# Tachometer-with-4x7-Segm-LED-Display.net
KiCad netlist of a schematic drawn in EAGLE
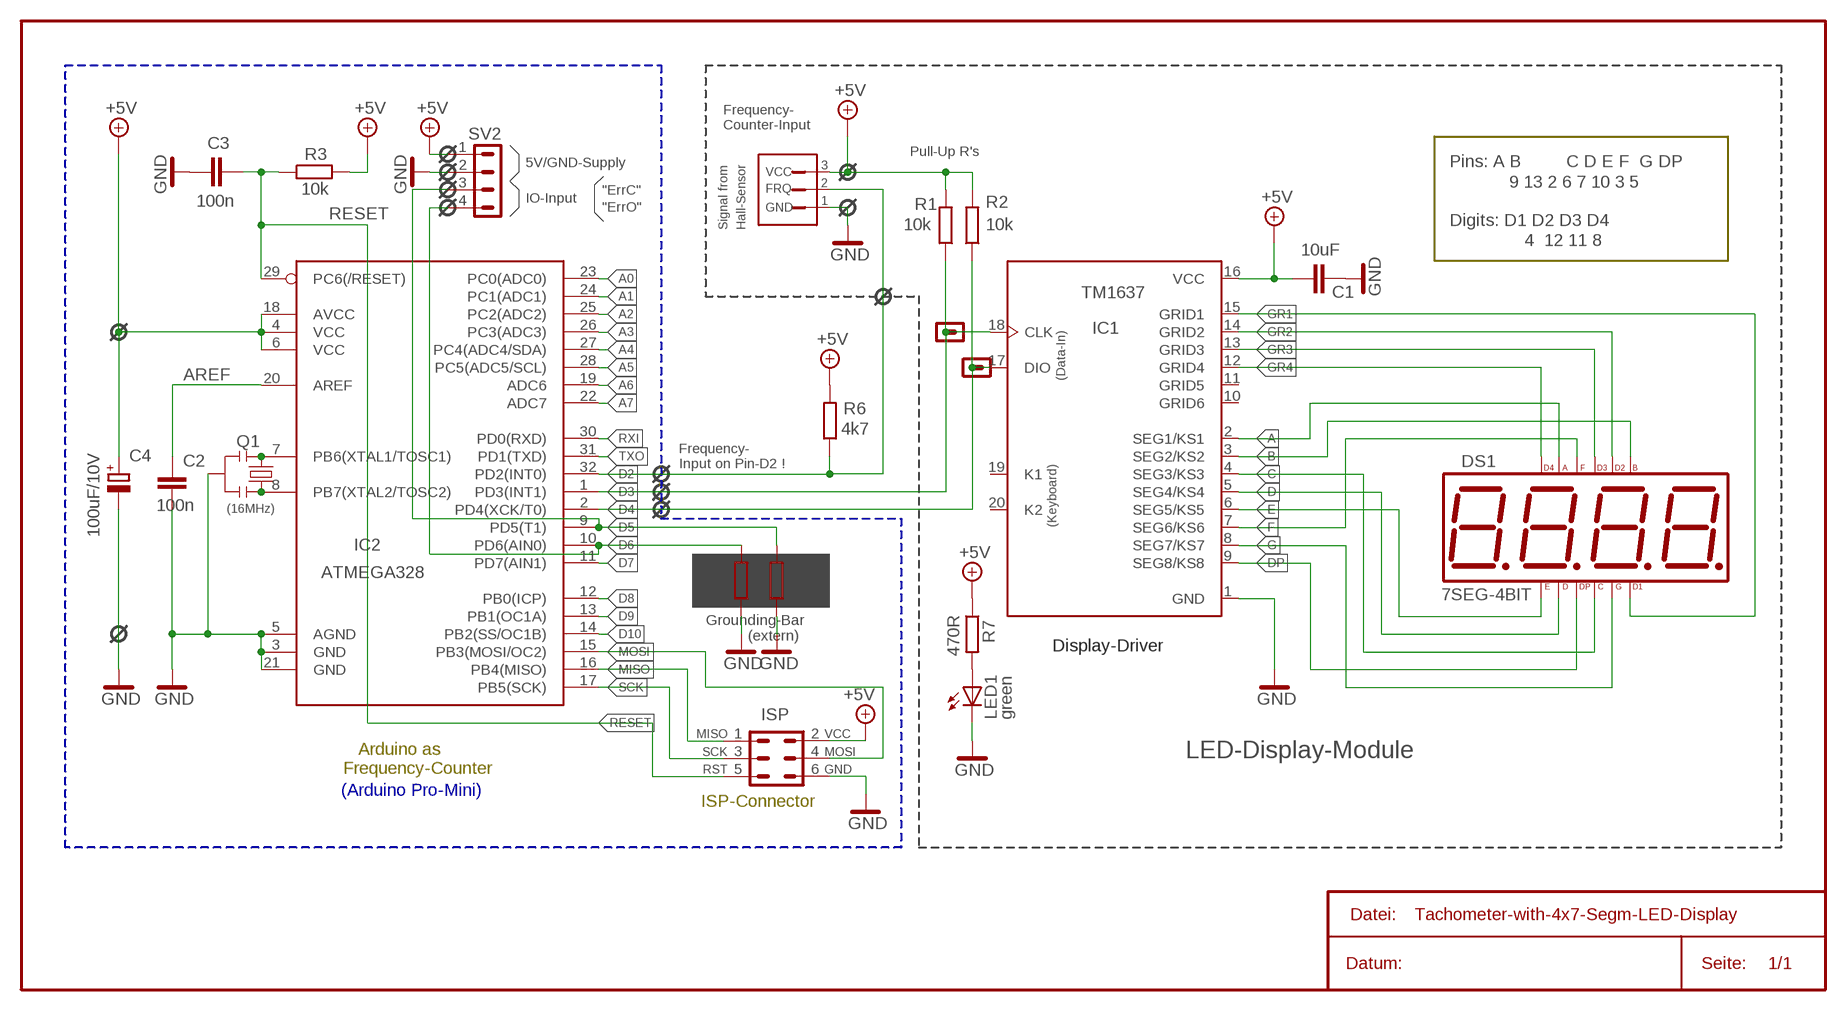
[diagram p0: schematic, sheet 1]

(export (version "E")
  (design (tool "Eeschema 10.0.6"))
  (components
    (comp (ref "C1")
      (value "10uF")
      (footprint "eagle-import:C0805")
      (libsource (lib "eagle-import") (part "C-EUC0805"))
    )
    (comp (ref "C2")
      (value "100n")
      (footprint "eagle-import:C0603")
      (libsource (lib "eagle-import") (part "C-EUC0603"))
    )
    (comp (ref "C3")
      (value "100n")
      (footprint "eagle-import:C0603")
      (libsource (lib "eagle-import") (part "C-EUC0603"))
    )
    (comp (ref "C4")
      (value "100uF/10V")
      (footprint "eagle-import:E2,5-7")
      (libsource (lib "eagle-import") (part "CPOL-EUE2.5-7"))
    )
    (comp (ref "DS1")
      (value "7SEG-4BIT")
      (footprint "eagle-import:7SEG-14-4BIT")
      (libsource (lib "eagle-import") (part "7SEG-4BT"))
    )
    (comp (ref "H")
      (value "Hall-Ss.")
      (footprint "eagle-import:3JST-XH")
      (libsource (lib "eagle-import") (part "3JST-XH"))
    )
    (comp (ref "IC1")
      (value "TM1637")
      (footprint "eagle-import:SOP-20")
      (libsource (lib "eagle-import") (part "TM1637"))
    )
    (comp (ref "IC2")
      (value "ATMEGA328")
      (footprint "eagle-import:TQFP32-08")
      (libsource (lib "eagle-import") (part "ATMEGA168"))
    )
    (comp (ref "ISP")
      (value "MA03-2")
      (footprint "eagle-import:MA03-2")
      (libsource (lib "eagle-import") (part "MA03-2"))
    )
    (comp (ref "LED1")
      (value "green")
      (footprint "eagle-import:CHIPLED_0603")
      (libsource (lib "eagle-import") (part "LEDCHIPLED_0603"))
    )
    (comp (ref "Q1")
      (value "(16MHz)")
      (footprint "eagle-import:RESONATOR-SMD-1_1")
      (libsource (lib "eagle-import") (part "RESONATOR1{colon}1"))
    )
    (comp (ref "R1")
      (value "10k")
      (footprint "eagle-import:R0603")
      (libsource (lib "eagle-import") (part "R-EU_R0603"))
    )
    (comp (ref "R2")
      (value "10k")
      (footprint "eagle-import:R0603")
      (libsource (lib "eagle-import") (part "R-EU_R0603"))
    )
    (comp (ref "R3")
      (value "10k")
      (footprint "eagle-import:R0603")
      (libsource (lib "eagle-import") (part "R-EU_R0603"))
    )
    (comp (ref "R4")
      (value "10k")
      (footprint "eagle-import:R0603")
      (libsource (lib "eagle-import") (part "R-EU_R0603"))
    )
    (comp (ref "R5")
      (value "10k")
      (footprint "eagle-import:R0603")
      (libsource (lib "eagle-import") (part "R-EU_R0603"))
    )
    (comp (ref "R6")
      (value "4k7")
      (footprint "eagle-import:R0603")
      (libsource (lib "eagle-import") (part "R-EU_R0603"))
    )
    (comp (ref "R7")
      (value "470R")
      (footprint "eagle-import:R0603")
      (libsource (lib "eagle-import") (part "R-EU_R0603"))
    )
    (comp (ref "SV2")
      (value "MA04-10")
      (footprint "eagle-import:MA04-1")
      (libsource (lib "eagle-import") (part "MA04-10"))
    )
  )
  (nets
    (net (code "1") (name "+5V") (class "Default")
      (node (ref "C1") (pin "1") (pinfunction "1_1") (pintype "passive"))
      (node (ref "C4") (pin "+") (pinfunction "+_+") (pintype "passive"))
      (node (ref "H") (pin "1") (pinfunction "1_1") (pintype "passive"))
      (node (ref "IC1") (pin "16") (pinfunction "VCC_16") (pintype "bidirectional"))
      (node (ref "IC2") (pin "18") (pinfunction "AVCC_18") (pintype "bidirectional"))
      (node (ref "IC2") (pin "4") (pinfunction "VCC_4") (pintype "bidirectional"))
      (node (ref "IC2") (pin "6") (pinfunction "VCC_6") (pintype "bidirectional"))
      (node (ref "ISP") (pin "2") (pinfunction "2_2") (pintype "passive"))
      (node (ref "R1") (pin "2") (pinfunction "2_2") (pintype "passive"))
      (node (ref "R2") (pin "2") (pinfunction "2_2") (pintype "passive"))
      (node (ref "R3") (pin "2") (pinfunction "2_2") (pintype "passive"))
      (node (ref "R6") (pin "2") (pinfunction "2_2") (pintype "passive"))
      (node (ref "R7") (pin "1") (pinfunction "1_1") (pintype "passive"))
      (node (ref "SV2") (pin "1") (pinfunction "1_1") (pintype "passive"))
    )
    (net (code "2") (name "/AREF") (class "Default")
      (node (ref "C2") (pin "1") (pinfunction "1_1") (pintype "passive"))
      (node (ref "IC2") (pin "20") (pinfunction "AREF_20") (pintype "bidirectional"))
    )
    (net (code "3") (name "A") (class "Default")
      (node (ref "DS1") (pin "A") (pinfunction "A_A") (pintype "bidirectional"))
      (node (ref "IC1") (pin "2") (pinfunction "SEG1/KS1_2") (pintype "bidirectional"))
    )
    (net (code "4") (name "A0") (class "Default")
      (node (ref "IC2") (pin "23") (pinfunction "PC0(ADC0)_23") (pintype "bidirectional"))
    )
    (net (code "5") (name "A1") (class "Default")
      (node (ref "IC2") (pin "24") (pinfunction "PC1(ADC1)_24") (pintype "bidirectional"))
    )
    (net (code "6") (name "A2") (class "Default")
      (node (ref "IC2") (pin "25") (pinfunction "PC2(ADC2)_25") (pintype "bidirectional"))
    )
    (net (code "7") (name "A3") (class "Default")
      (node (ref "IC2") (pin "26") (pinfunction "PC3(ADC3)_26") (pintype "bidirectional"))
    )
    (net (code "8") (name "A4") (class "Default")
      (node (ref "IC2") (pin "27") (pinfunction "PC4(ADC4/SDA)_27") (pintype "bidirectional"))
    )
    (net (code "9") (name "A5") (class "Default")
      (node (ref "IC2") (pin "28") (pinfunction "PC5(ADC5/SCL)_28") (pintype "bidirectional"))
    )
    (net (code "10") (name "A6") (class "Default")
      (node (ref "IC2") (pin "19") (pinfunction "ADC6_19") (pintype "bidirectional"))
    )
    (net (code "11") (name "A7") (class "Default")
      (node (ref "IC2") (pin "22") (pinfunction "ADC7_22") (pintype "bidirectional"))
    )
    (net (code "12") (name "B") (class "Default")
      (node (ref "DS1") (pin "B") (pinfunction "B_B") (pintype "bidirectional"))
      (node (ref "IC1") (pin "3") (pinfunction "SEG2/KS2_3") (pintype "bidirectional"))
    )
    (net (code "13") (name "C") (class "Default")
      (node (ref "DS1") (pin "C") (pinfunction "C_C") (pintype "bidirectional"))
      (node (ref "IC1") (pin "4") (pinfunction "SEG3/KS3_4") (pintype "bidirectional"))
    )
    (net (code "14") (name "D") (class "Default")
      (node (ref "DS1") (pin "D") (pinfunction "D_D") (pintype "bidirectional"))
      (node (ref "IC1") (pin "5") (pinfunction "SEG4/KS4_5") (pintype "bidirectional"))
    )
    (net (code "15") (name "D2") (class "Default")
      (node (ref "H") (pin "2") (pinfunction "1_2") (pintype "passive"))
      (node (ref "IC2") (pin "32") (pinfunction "PD2(INT0)_32") (pintype "bidirectional"))
      (node (ref "R6") (pin "1") (pinfunction "1_1") (pintype "passive"))
    )
    (net (code "16") (name "D3") (class "Default")
      (node (ref "IC1") (pin "18") (pinfunction "CLK_18") (pintype "bidirectional"))
      (node (ref "IC2") (pin "1") (pinfunction "PD3(INT1)_1") (pintype "bidirectional"))
      (node (ref "R1") (pin "1") (pinfunction "1_1") (pintype "passive"))
    )
    (net (code "17") (name "D4") (class "Default")
      (node (ref "IC1") (pin "17") (pinfunction "DIO_17") (pintype "bidirectional"))
      (node (ref "IC2") (pin "2") (pinfunction "PD4(XCK/T0)_2") (pintype "bidirectional"))
      (node (ref "R2") (pin "1") (pinfunction "1_1") (pintype "passive"))
    )
    (net (code "18") (name "D5") (class "Default")
      (node (ref "IC2") (pin "9") (pinfunction "PD5(T1)_9") (pintype "bidirectional"))
      (node (ref "R5") (pin "2") (pinfunction "2_2") (pintype "passive"))
      (node (ref "SV2") (pin "3") (pinfunction "3_3") (pintype "passive"))
    )
    (net (code "19") (name "D6") (class "Default")
      (node (ref "IC2") (pin "10") (pinfunction "PD6(AIN0)_10") (pintype "bidirectional"))
      (node (ref "R4") (pin "2") (pinfunction "2_2") (pintype "passive"))
      (node (ref "SV2") (pin "4") (pinfunction "4_4") (pintype "passive"))
    )
    (net (code "20") (name "D7") (class "Default")
      (node (ref "IC2") (pin "11") (pinfunction "PD7(AIN1)_11") (pintype "bidirectional"))
    )
    (net (code "21") (name "D8") (class "Default")
      (node (ref "IC2") (pin "12") (pinfunction "PB0(ICP)_12") (pintype "bidirectional"))
    )
    (net (code "22") (name "D9") (class "Default")
      (node (ref "IC2") (pin "13") (pinfunction "PB1(OC1A)_13") (pintype "bidirectional"))
    )
    (net (code "23") (name "D10") (class "Default")
      (node (ref "IC2") (pin "14") (pinfunction "PB2(SS/OC1B)_14") (pintype "bidirectional"))
    )
    (net (code "24") (name "DP") (class "Default")
      (node (ref "DS1") (pin "DP") (pinfunction "DP_DP") (pintype "bidirectional"))
      (node (ref "IC1") (pin "9") (pinfunction "SEG8/KS8_9") (pintype "bidirectional"))
    )
    (net (code "25") (name "E") (class "Default")
      (node (ref "DS1") (pin "E") (pinfunction "E_E") (pintype "bidirectional"))
      (node (ref "IC1") (pin "6") (pinfunction "SEG5/KS5_6") (pintype "bidirectional"))
    )
    (net (code "26") (name "F") (class "Default")
      (node (ref "DS1") (pin "F") (pinfunction "F_F") (pintype "bidirectional"))
      (node (ref "IC1") (pin "7") (pinfunction "SEG6/KS6_7") (pintype "bidirectional"))
    )
    (net (code "27") (name "G") (class "Default")
      (node (ref "DS1") (pin "G") (pinfunction "G_G") (pintype "bidirectional"))
      (node (ref "IC1") (pin "8") (pinfunction "SEG7/KS7_8") (pintype "bidirectional"))
    )
    (net (code "28") (name "GND") (class "Default")
      (node (ref "C1") (pin "2") (pinfunction "2_2") (pintype "passive"))
      (node (ref "C2") (pin "2") (pinfunction "2_2") (pintype "passive"))
      (node (ref "C3") (pin "1") (pinfunction "1_1") (pintype "passive"))
      (node (ref "C4") (pin "-") (pinfunction "-_-") (pintype "passive"))
      (node (ref "H") (pin "3") (pinfunction "1_3") (pintype "passive"))
      (node (ref "IC1") (pin "1") (pinfunction "GND_1") (pintype "bidirectional"))
      (node (ref "IC2") (pin "21") (pinfunction "GND_21") (pintype "bidirectional"))
      (node (ref "IC2") (pin "3") (pinfunction "GND_3") (pintype "bidirectional"))
      (node (ref "IC2") (pin "5") (pinfunction "AGND_5") (pintype "bidirectional"))
      (node (ref "ISP") (pin "6") (pinfunction "6_6") (pintype "passive"))
      (node (ref "LED1") (pin "C") (pinfunction "C_C") (pintype "passive"))
      (node (ref "Q1") (pin "2") (pinfunction "2_2") (pintype "passive"))
      (node (ref "R4") (pin "1") (pinfunction "1_1") (pintype "passive"))
      (node (ref "R5") (pin "1") (pinfunction "1_1") (pintype "passive"))
      (node (ref "SV2") (pin "2") (pinfunction "2_2") (pintype "passive"))
    )
    (net (code "29") (name "GR1") (class "Default")
      (node (ref "DS1") (pin "D1") (pinfunction "D1_D1") (pintype "bidirectional"))
      (node (ref "IC1") (pin "15") (pinfunction "GRID1_15") (pintype "bidirectional"))
    )
    (net (code "30") (name "GR2") (class "Default")
      (node (ref "DS1") (pin "D2") (pinfunction "D2_D2") (pintype "bidirectional"))
      (node (ref "IC1") (pin "14") (pinfunction "GRID2_14") (pintype "bidirectional"))
    )
    (net (code "31") (name "GR3") (class "Default")
      (node (ref "DS1") (pin "D3") (pinfunction "D3_D3") (pintype "bidirectional"))
      (node (ref "IC1") (pin "13") (pinfunction "GRID3_13") (pintype "bidirectional"))
    )
    (net (code "32") (name "GR4") (class "Default")
      (node (ref "DS1") (pin "D4") (pinfunction "D4_D4") (pintype "bidirectional"))
      (node (ref "IC1") (pin "12") (pinfunction "GRID4_12") (pintype "bidirectional"))
    )
    (net (code "33") (name "MISO") (class "Default")
      (node (ref "IC2") (pin "16") (pinfunction "PB4(MISO)_16") (pintype "bidirectional"))
      (node (ref "ISP") (pin "1") (pinfunction "1_1") (pintype "passive"))
    )
    (net (code "34") (name "MOSI") (class "Default")
      (node (ref "IC2") (pin "15") (pinfunction "PB3(MOSI/OC2)_15") (pintype "bidirectional"))
      (node (ref "ISP") (pin "4") (pinfunction "4_4") (pintype "passive"))
    )
    (net (code "35") (name "Net-(IC2-PB6(XTAL1{slash}TOSC1))") (class "Default")
      (node (ref "IC2") (pin "7") (pinfunction "PB6(XTAL1/TOSC1)_7") (pintype "bidirectional"))
      (node (ref "Q1") (pin "1") (pinfunction "1_1") (pintype "passive"))
    )
    (net (code "36") (name "Net-(IC2-PB7(XTAL2{slash}TOSC2))") (class "Default")
      (node (ref "IC2") (pin "8") (pinfunction "PB7(XTAL2/TOSC2)_8") (pintype "bidirectional"))
      (node (ref "Q1") (pin "3") (pinfunction "3_3") (pintype "passive"))
    )
    (net (code "37") (name "Net-(LED1-PadA)") (class "Default")
      (node (ref "LED1") (pin "A") (pinfunction "A_A") (pintype "passive"))
      (node (ref "R7") (pin "2") (pinfunction "2_2") (pintype "passive"))
    )
    (net (code "38") (name "RESET") (class "Default")
      (node (ref "C3") (pin "2") (pinfunction "2_2") (pintype "passive"))
      (node (ref "IC2") (pin "29") (pinfunction "PC6(/RESET)_29") (pintype "bidirectional"))
      (node (ref "ISP") (pin "5") (pinfunction "5_5") (pintype "passive"))
      (node (ref "R3") (pin "1") (pinfunction "1_1") (pintype "passive"))
    )
    (net (code "39") (name "RXI") (class "Default")
      (node (ref "IC2") (pin "30") (pinfunction "PD0(RXD)_30") (pintype "bidirectional"))
    )
    (net (code "40") (name "SCK") (class "Default")
      (node (ref "IC2") (pin "17") (pinfunction "PB5(SCK)_17") (pintype "bidirectional"))
      (node (ref "ISP") (pin "3") (pinfunction "3_3") (pintype "passive"))
    )
    (net (code "41") (name "TXO") (class "Default")
      (node (ref "IC2") (pin "31") (pinfunction "PD1(TXD)_31") (pintype "bidirectional"))
    )
    (net (code "42") (name "unconnected-(IC1-GRID5-Pad11)") (class "Default")
      (node (ref "IC1") (pin "11") (pinfunction "GRID5_11") (pintype "bidirectional"))
    )
    (net (code "43") (name "unconnected-(IC1-GRID6-Pad10)") (class "Default")
      (node (ref "IC1") (pin "10") (pinfunction "GRID6_10") (pintype "bidirectional"))
    )
    (net (code "44") (name "unconnected-(IC1-K1-Pad19)") (class "Default")
      (node (ref "IC1") (pin "19") (pinfunction "K1_19") (pintype "bidirectional"))
    )
    (net (code "45") (name "unconnected-(IC1-K2-Pad20)") (class "Default")
      (node (ref "IC1") (pin "20") (pinfunction "K2_20") (pintype "bidirectional"))
    )
  )
)
